# TLE6244x.net
KiCad netlist of a schematic drawn in Altium Designer
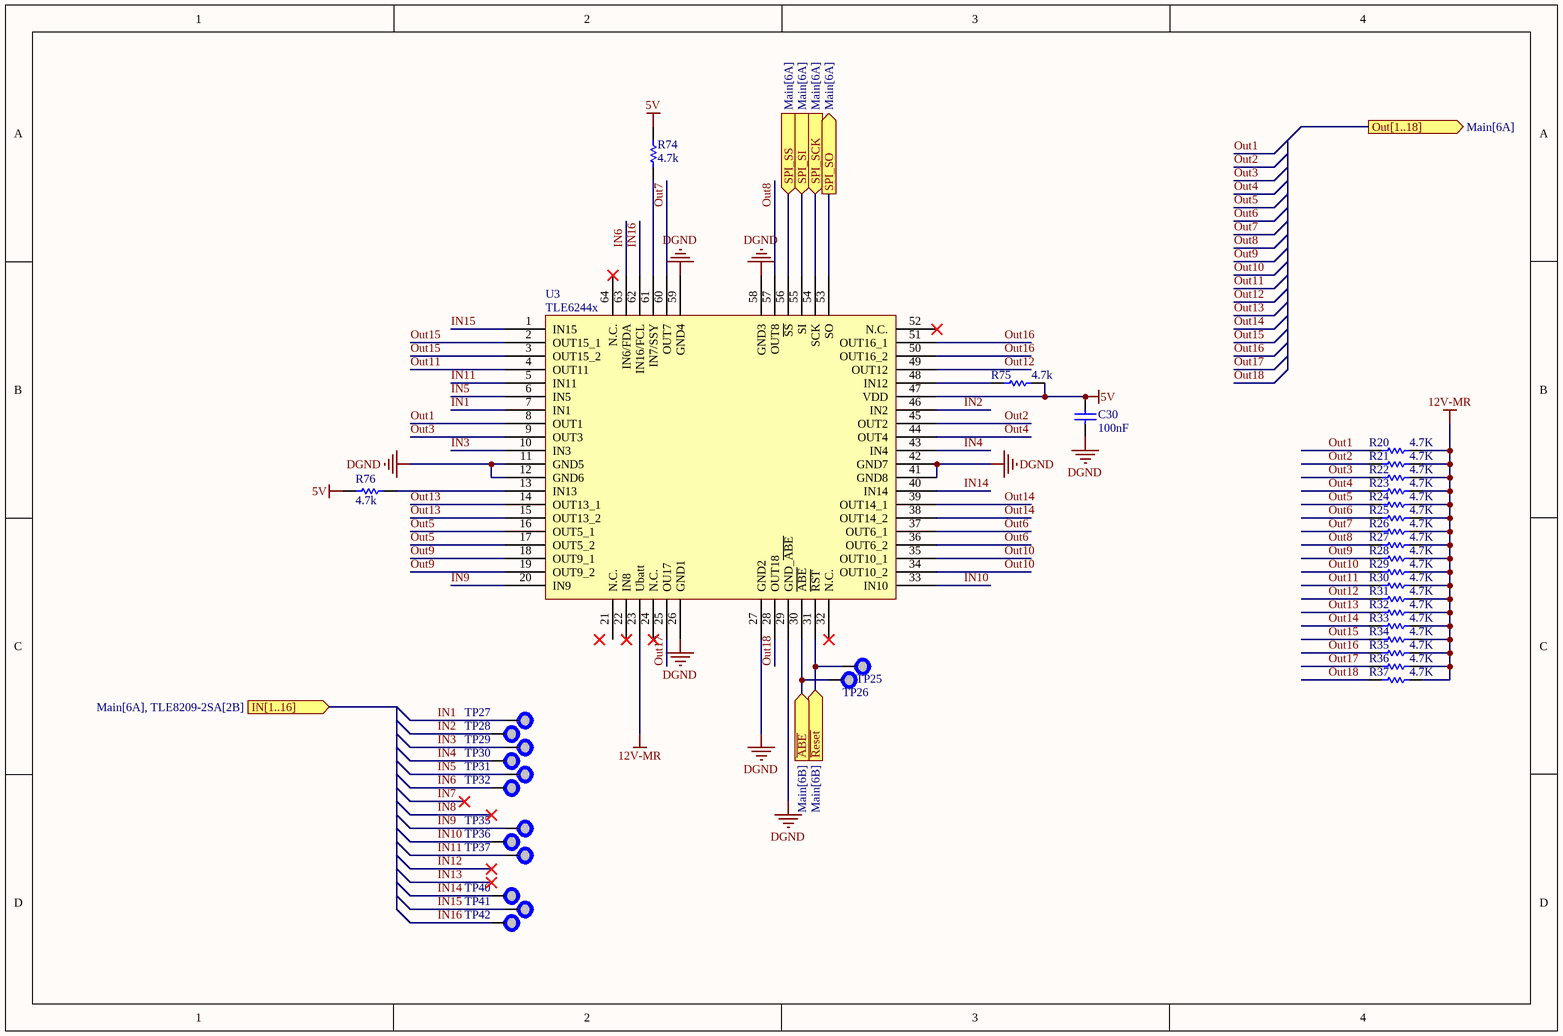
[diagram p0: TLE6244x.SchDoc]

(export (version "E")
  (design (tool "Eeschema 10.0.6"))
  (components
    (comp (ref "C30")
      (value "100nF")
      (footprint "0603C")
      (description "Capacitor")
      (fields (field (name "Comment") "CGA3E2X7R1H104K080AA") (field (name "PUBLISHER") "Altium Limited"))
      (libsource (lib "Miscellaneous Devices") (part "Cap"))
    )
    (comp (ref "R20")
      (value "4.7K")
      (footprint "0805")
      (description "Resistor")
      (fields (field (name "Comment") "Res1") (field (name "PUBLISHER") "Altium Limited"))
      (libsource (lib "Miscellaneous Devices") (part "Res1"))
    )
    (comp (ref "R21")
      (value "4.7K")
      (footprint "0805")
      (description "Resistor")
      (fields (field (name "Comment") "Res1") (field (name "PUBLISHER") "Altium Limited"))
      (libsource (lib "Miscellaneous Devices") (part "Res1"))
    )
    (comp (ref "R22")
      (value "4.7K")
      (footprint "0805")
      (description "Resistor")
      (fields (field (name "Comment") "Res1") (field (name "PUBLISHER") "Altium Limited"))
      (libsource (lib "Miscellaneous Devices") (part "Res1"))
    )
    (comp (ref "R23")
      (value "4.7K")
      (footprint "0805")
      (description "Resistor")
      (fields (field (name "Comment") "Res1") (field (name "PUBLISHER") "Altium Limited"))
      (libsource (lib "Miscellaneous Devices") (part "Res1"))
    )
    (comp (ref "R24")
      (value "4.7K")
      (footprint "0805")
      (description "Resistor")
      (fields (field (name "Comment") "Res1") (field (name "PUBLISHER") "Altium Limited"))
      (libsource (lib "Miscellaneous Devices") (part "Res1"))
    )
    (comp (ref "R25")
      (value "4.7K")
      (footprint "0805")
      (description "Resistor")
      (fields (field (name "Comment") "Res1") (field (name "PUBLISHER") "Altium Limited"))
      (libsource (lib "Miscellaneous Devices") (part "Res1"))
    )
    (comp (ref "R26")
      (value "4.7K")
      (footprint "0805")
      (description "Resistor")
      (fields (field (name "Comment") "Res1") (field (name "PUBLISHER") "Altium Limited"))
      (libsource (lib "Miscellaneous Devices") (part "Res1"))
    )
    (comp (ref "R27")
      (value "4.7K")
      (footprint "0805")
      (description "Resistor")
      (fields (field (name "Comment") "Res1") (field (name "PUBLISHER") "Altium Limited"))
      (libsource (lib "Miscellaneous Devices") (part "Res1"))
    )
    (comp (ref "R28")
      (value "4.7K")
      (footprint "0805")
      (description "Resistor")
      (fields (field (name "Comment") "Res1") (field (name "PUBLISHER") "Altium Limited"))
      (libsource (lib "Miscellaneous Devices") (part "Res1"))
    )
    (comp (ref "R29")
      (value "4.7K")
      (footprint "0805")
      (description "Resistor")
      (fields (field (name "Comment") "Res1") (field (name "PUBLISHER") "Altium Limited"))
      (libsource (lib "Miscellaneous Devices") (part "Res1"))
    )
    (comp (ref "R30")
      (value "4.7K")
      (footprint "0805")
      (description "Resistor")
      (fields (field (name "Comment") "Res1") (field (name "PUBLISHER") "Altium Limited"))
      (libsource (lib "Miscellaneous Devices") (part "Res1"))
    )
    (comp (ref "R31")
      (value "4.7K")
      (footprint "0805")
      (description "Resistor")
      (fields (field (name "Comment") "Res1") (field (name "PUBLISHER") "Altium Limited"))
      (libsource (lib "Miscellaneous Devices") (part "Res1"))
    )
    (comp (ref "R32")
      (value "4.7K")
      (footprint "0805")
      (description "Resistor")
      (fields (field (name "Comment") "Res1") (field (name "PUBLISHER") "Altium Limited"))
      (libsource (lib "Miscellaneous Devices") (part "Res1"))
    )
    (comp (ref "R33")
      (value "4.7K")
      (footprint "0805")
      (description "Resistor")
      (fields (field (name "Comment") "Res1") (field (name "PUBLISHER") "Altium Limited"))
      (libsource (lib "Miscellaneous Devices") (part "Res1"))
    )
    (comp (ref "R34")
      (value "4.7K")
      (footprint "0805")
      (description "Resistor")
      (fields (field (name "Comment") "Res1") (field (name "PUBLISHER") "Altium Limited"))
      (libsource (lib "Miscellaneous Devices") (part "Res1"))
    )
    (comp (ref "R35")
      (value "4.7K")
      (footprint "0805")
      (description "Resistor")
      (fields (field (name "Comment") "Res1") (field (name "PUBLISHER") "Altium Limited"))
      (libsource (lib "Miscellaneous Devices") (part "Res1"))
    )
    (comp (ref "R36")
      (value "4.7K")
      (footprint "0805")
      (description "Resistor")
      (fields (field (name "Comment") "Res1") (field (name "PUBLISHER") "Altium Limited"))
      (libsource (lib "Miscellaneous Devices") (part "Res1"))
    )
    (comp (ref "R37")
      (value "4.7K")
      (footprint "0805")
      (description "Resistor")
      (fields (field (name "Comment") "Res1") (field (name "PUBLISHER") "Altium Limited"))
      (libsource (lib "Miscellaneous Devices") (part "Res1"))
    )
    (comp (ref "R74")
      (value "4.7k")
      (footprint "0805")
      (description "Resistor")
      (fields (field (name "Comment") "Res1") (field (name "PUBLISHER") "Altium Limited"))
      (libsource (lib "Miscellaneous Devices") (part "Res1"))
    )
    (comp (ref "R75")
      (value "4.7k")
      (footprint "0805")
      (description "Resistor")
      (fields (field (name "Comment") "Res1") (field (name "PUBLISHER") "Altium Limited"))
      (libsource (lib "Miscellaneous Devices") (part "Res1"))
    )
    (comp (ref "R76")
      (value "4.7k")
      (footprint "0805")
      (description "Resistor")
      (fields (field (name "Comment") "Res1") (field (name "PUBLISHER") "Altium Limited"))
      (libsource (lib "Miscellaneous Devices") (part "Res1"))
    )
    (comp (ref "TP25") (value "TestPoint") (footprint "TP") (libsource (lib "SchlibV0.1") (part "TestPoint")))
    (comp (ref "TP26") (value "TestPoint") (footprint "TP") (libsource (lib "SchlibV0.1") (part "TestPoint")))
    (comp (ref "TP27") (value "TestPoint") (footprint "TP") (libsource (lib "SchlibV0.1") (part "TestPoint")))
    (comp (ref "TP28") (value "TestPoint") (footprint "TP") (libsource (lib "SchlibV0.1") (part "TestPoint")))
    (comp (ref "TP29") (value "TestPoint") (footprint "TP") (libsource (lib "SchlibV0.1") (part "TestPoint")))
    (comp (ref "TP30") (value "TestPoint") (footprint "TP") (libsource (lib "SchlibV0.1") (part "TestPoint")))
    (comp (ref "TP31") (value "TestPoint") (footprint "TP") (libsource (lib "SchlibV0.1") (part "TestPoint")))
    (comp (ref "TP32") (value "TestPoint") (footprint "TP") (libsource (lib "SchlibV0.1") (part "TestPoint")))
    (comp (ref "TP35") (value "TestPoint") (footprint "TP") (libsource (lib "SchlibV0.1") (part "TestPoint")))
    (comp (ref "TP36") (value "TestPoint") (footprint "TP") (libsource (lib "SchlibV0.1") (part "TestPoint")))
    (comp (ref "TP37") (value "TestPoint") (footprint "TP") (libsource (lib "SchlibV0.1") (part "TestPoint")))
    (comp (ref "TP40") (value "TestPoint") (footprint "TP") (libsource (lib "SchlibV0.1") (part "TestPoint")))
    (comp (ref "TP41") (value "TestPoint") (footprint "TP") (libsource (lib "SchlibV0.1") (part "TestPoint")))
    (comp (ref "TP42") (value "TestPoint") (footprint "TP") (libsource (lib "SchlibV0.1") (part "TestPoint")))
    (comp (ref "U3")
      (value "TLE6244x")
      (footprint "TLE6244")
      (description "PG-MQFP-64-10")
      (fields (field (name "MANUFACTURER") "Infineon") (field (name "PART NUMBER") "TLE6244X"))
      (libsource (lib "TLE 6244X") (part "TLE6244x"))
    )
  )
  (nets
    (net (code "1") (name "/IN1") (class "Default")
      (node (ref "TP27") (pin "1") (pintype "passive"))
      (node (ref "U3") (pin "7") (pinfunction "IN1_7") (pintype "passive"))
    )
    (net (code "2") (name "/IN2") (class "Default")
      (node (ref "TP28") (pin "1") (pintype "passive"))
      (node (ref "U3") (pin "46") (pinfunction "IN2_46") (pintype "passive"))
    )
    (net (code "3") (name "/IN3") (class "Default")
      (node (ref "TP29") (pin "1") (pintype "passive"))
      (node (ref "U3") (pin "10") (pinfunction "IN3_10") (pintype "passive"))
    )
    (net (code "4") (name "/IN4") (class "Default")
      (node (ref "TP30") (pin "1") (pintype "passive"))
      (node (ref "U3") (pin "43") (pinfunction "IN4_43") (pintype "passive"))
    )
    (net (code "5") (name "/IN5") (class "Default")
      (node (ref "TP31") (pin "1") (pintype "passive"))
      (node (ref "U3") (pin "6") (pinfunction "IN5_6") (pintype "passive"))
    )
    (net (code "6") (name "/IN6") (class "Default")
      (node (ref "TP32") (pin "1") (pintype "passive"))
      (node (ref "U3") (pin "63") (pinfunction "IN6/FDA_63") (pintype "passive"))
    )
    (net (code "9") (name "/IN9") (class "Default")
      (node (ref "TP35") (pin "1") (pintype "passive"))
      (node (ref "U3") (pin "20") (pinfunction "IN9_20") (pintype "passive"))
    )
    (net (code "10") (name "/IN10") (class "Default")
      (node (ref "TP36") (pin "1") (pintype "passive"))
      (node (ref "U3") (pin "33") (pinfunction "IN10_33") (pintype "passive"))
    )
    (net (code "11") (name "/IN11") (class "Default")
      (node (ref "TP37") (pin "1") (pintype "passive"))
      (node (ref "U3") (pin "5") (pinfunction "IN11_5") (pintype "passive"))
    )
    (net (code "14") (name "/IN14") (class "Default")
      (node (ref "TP40") (pin "1") (pintype "passive"))
      (node (ref "U3") (pin "40") (pinfunction "IN14_40") (pintype "passive"))
    )
    (net (code "15") (name "/IN15") (class "Default")
      (node (ref "TP41") (pin "1") (pintype "passive"))
      (node (ref "U3") (pin "1") (pinfunction "IN15_1") (pintype "passive"))
    )
    (net (code "16") (name "/IN16") (class "Default")
      (node (ref "TP42") (pin "1") (pintype "passive"))
      (node (ref "U3") (pin "62") (pinfunction "IN16/FCL_62") (pintype "passive"))
    )
    (net (code "18") (name "/Out1") (class "Default")
      (node (ref "R20") (pin "2") (pinfunction "2_2") (pintype "passive"))
      (node (ref "U3") (pin "8") (pinfunction "OUT1_8") (pintype "passive"))
    )
    (net (code "19") (name "/Out2") (class "Default")
      (node (ref "R21") (pin "2") (pinfunction "2_2") (pintype "passive"))
      (node (ref "U3") (pin "45") (pinfunction "OUT2_45") (pintype "passive"))
    )
    (net (code "20") (name "/Out3") (class "Default")
      (node (ref "R22") (pin "2") (pinfunction "2_2") (pintype "passive"))
      (node (ref "U3") (pin "9") (pinfunction "OUT3_9") (pintype "passive"))
    )
    (net (code "21") (name "/Out4") (class "Default")
      (node (ref "R23") (pin "2") (pinfunction "2_2") (pintype "passive"))
      (node (ref "U3") (pin "44") (pinfunction "OUT4_44") (pintype "passive"))
    )
    (net (code "22") (name "/Out5") (class "Default")
      (node (ref "R24") (pin "2") (pinfunction "2_2") (pintype "passive"))
      (node (ref "U3") (pin "16") (pinfunction "OUT5_1_16") (pintype "passive"))
      (node (ref "U3") (pin "17") (pinfunction "OUT5_2_17") (pintype "passive"))
    )
    (net (code "23") (name "/Out6") (class "Default")
      (node (ref "R25") (pin "2") (pinfunction "2_2") (pintype "passive"))
      (node (ref "U3") (pin "36") (pinfunction "OUT6_2_36") (pintype "passive"))
      (node (ref "U3") (pin "37") (pinfunction "OUT6_1_37") (pintype "passive"))
    )
    (net (code "24") (name "/Out7") (class "Default")
      (node (ref "R26") (pin "2") (pinfunction "2_2") (pintype "passive"))
      (node (ref "U3") (pin "60") (pinfunction "OUT7_60") (pintype "passive"))
    )
    (net (code "25") (name "/Out8") (class "Default")
      (node (ref "R27") (pin "2") (pinfunction "2_2") (pintype "passive"))
      (node (ref "U3") (pin "57") (pinfunction "OUT8_57") (pintype "passive"))
    )
    (net (code "26") (name "/Out9") (class "Default")
      (node (ref "R28") (pin "2") (pinfunction "2_2") (pintype "passive"))
      (node (ref "U3") (pin "18") (pinfunction "OUT9_1_18") (pintype "passive"))
      (node (ref "U3") (pin "19") (pinfunction "OUT9_2_19") (pintype "passive"))
    )
    (net (code "27") (name "/Out10") (class "Default")
      (node (ref "R29") (pin "2") (pinfunction "2_2") (pintype "passive"))
      (node (ref "U3") (pin "34") (pinfunction "OUT10_2_34") (pintype "passive"))
      (node (ref "U3") (pin "35") (pinfunction "OUT10_1_35") (pintype "passive"))
    )
    (net (code "28") (name "/Out11") (class "Default")
      (node (ref "R30") (pin "2") (pinfunction "2_2") (pintype "passive"))
      (node (ref "U3") (pin "4") (pinfunction "OUT11_4") (pintype "passive"))
    )
    (net (code "29") (name "/Out12") (class "Default")
      (node (ref "R31") (pin "2") (pinfunction "2_2") (pintype "passive"))
      (node (ref "U3") (pin "49") (pinfunction "OUT12_49") (pintype "passive"))
    )
    (net (code "30") (name "/Out13") (class "Default")
      (node (ref "R32") (pin "2") (pinfunction "2_2") (pintype "passive"))
      (node (ref "U3") (pin "14") (pinfunction "OUT13_1_14") (pintype "passive"))
      (node (ref "U3") (pin "15") (pinfunction "OUT13_2_15") (pintype "passive"))
    )
    (net (code "31") (name "/Out14") (class "Default")
      (node (ref "R33") (pin "2") (pinfunction "2_2") (pintype "passive"))
      (node (ref "U3") (pin "38") (pinfunction "OUT14_2_38") (pintype "passive"))
      (node (ref "U3") (pin "39") (pinfunction "OUT14_1_39") (pintype "passive"))
    )
    (net (code "32") (name "/Out15") (class "Default")
      (node (ref "R34") (pin "2") (pinfunction "2_2") (pintype "passive"))
      (node (ref "U3") (pin "2") (pinfunction "OUT15_1_2") (pintype "passive"))
      (node (ref "U3") (pin "3") (pinfunction "OUT15_2_3") (pintype "passive"))
    )
    (net (code "33") (name "/Out16") (class "Default")
      (node (ref "R35") (pin "2") (pinfunction "2_2") (pintype "passive"))
      (node (ref "U3") (pin "50") (pinfunction "OUT16_2_50") (pintype "passive"))
      (node (ref "U3") (pin "51") (pinfunction "OUT16_1_51") (pintype "passive"))
    )
    (net (code "34") (name "/Out17") (class "Default")
      (node (ref "R36") (pin "2") (pinfunction "2_2") (pintype "passive"))
      (node (ref "U3") (pin "25") (pinfunction "OU17_25") (pintype "passive"))
    )
    (net (code "35") (name "/Out18") (class "Default")
      (node (ref "R37") (pin "2") (pinfunction "2_2") (pintype "passive"))
      (node (ref "U3") (pin "28") (pinfunction "OUT18_28") (pintype "passive"))
    )
    (net (code "37") (name "/SPI_SCK") (class "Default")
      (node (ref "U3") (pin "54") (pinfunction "SCK_54") (pintype "passive"))
    )
    (net (code "38") (name "/SPI_SI") (class "Default")
      (node (ref "U3") (pin "55") (pinfunction "SI_55") (pintype "passive"))
    )
    (net (code "39") (name "/SPI_SO") (class "Default")
      (node (ref "U3") (pin "53") (pinfunction "SO_53") (pintype "passive"))
    )
    (net (code "40") (name "/SPI_SS") (class "Default")
      (node (ref "U3") (pin "56") (pinfunction "~{SS}_56") (pintype "passive"))
    )
    (net (code "41") (name "/~{ABE}") (class "Default")
      (node (ref "TP26") (pin "1") (pintype "passive"))
      (node (ref "U3") (pin "30") (pinfunction "~{ABE}_30") (pintype "passive"))
    )
    (net (code "42") (name "/~{Reset}") (class "Default")
      (node (ref "TP25") (pin "1") (pintype "passive"))
      (node (ref "U3") (pin "31") (pinfunction "~{RST}_31") (pintype "passive"))
    )
    (net (code "43") (name "5V") (class "Default")
      (node (ref "C30") (pin "1") (pinfunction "1_1") (pintype "passive"))
      (node (ref "R74") (pin "2") (pinfunction "2_2") (pintype "passive"))
      (node (ref "R75") (pin "1") (pinfunction "1_1") (pintype "passive"))
      (node (ref "R76") (pin "2") (pinfunction "2_2") (pintype "passive"))
      (node (ref "U3") (pin "47") (pinfunction "VDD_47") (pintype "passive"))
    )
    (net (code "44") (name "12V-MR") (class "Default")
      (node (ref "R20") (pin "1") (pinfunction "1_1") (pintype "passive"))
      (node (ref "R21") (pin "1") (pinfunction "1_1") (pintype "passive"))
      (node (ref "R22") (pin "1") (pinfunction "1_1") (pintype "passive"))
      (node (ref "R23") (pin "1") (pinfunction "1_1") (pintype "passive"))
      (node (ref "R24") (pin "1") (pinfunction "1_1") (pintype "passive"))
      (node (ref "R25") (pin "1") (pinfunction "1_1") (pintype "passive"))
      (node (ref "R26") (pin "1") (pinfunction "1_1") (pintype "passive"))
      (node (ref "R27") (pin "1") (pinfunction "1_1") (pintype "passive"))
      (node (ref "R28") (pin "1") (pinfunction "1_1") (pintype "passive"))
      (node (ref "R29") (pin "1") (pinfunction "1_1") (pintype "passive"))
      (node (ref "R30") (pin "1") (pinfunction "1_1") (pintype "passive"))
      (node (ref "R31") (pin "1") (pinfunction "1_1") (pintype "passive"))
      (node (ref "R32") (pin "1") (pinfunction "1_1") (pintype "passive"))
      (node (ref "R33") (pin "1") (pinfunction "1_1") (pintype "passive"))
      (node (ref "R34") (pin "1") (pinfunction "1_1") (pintype "passive"))
      (node (ref "R35") (pin "1") (pinfunction "1_1") (pintype "passive"))
      (node (ref "R36") (pin "1") (pinfunction "1_1") (pintype "passive"))
      (node (ref "R37") (pin "1") (pinfunction "1_1") (pintype "passive"))
      (node (ref "U3") (pin "23") (pinfunction "Ubatt_23") (pintype "passive"))
    )
    (net (code "45") (name "DGND") (class "Default")
      (node (ref "C30") (pin "2") (pinfunction "2_2") (pintype "passive"))
      (node (ref "U3") (pin "11") (pinfunction "GND5_11") (pintype "passive"))
      (node (ref "U3") (pin "12") (pinfunction "GND6_12") (pintype "passive"))
      (node (ref "U3") (pin "26") (pinfunction "GND1_26") (pintype "passive"))
      (node (ref "U3") (pin "27") (pinfunction "GND2_27") (pintype "passive"))
      (node (ref "U3") (pin "29") (pinfunction "GND_~{ABE}_29") (pintype "passive"))
      (node (ref "U3") (pin "41") (pinfunction "GND8_41") (pintype "passive"))
      (node (ref "U3") (pin "42") (pinfunction "GND7_42") (pintype "passive"))
      (node (ref "U3") (pin "58") (pinfunction "GND3_58") (pintype "passive"))
      (node (ref "U3") (pin "59") (pinfunction "GND4_59") (pintype "passive"))
    )
    (net (code "46") (name "Net-(U3-IN7{slash}SSY)") (class "Default")
      (node (ref "R74") (pin "1") (pinfunction "1_1") (pintype "passive"))
      (node (ref "U3") (pin "61") (pinfunction "IN7/SSY_61") (pintype "passive"))
    )
    (net (code "47") (name "Net-(U3-IN12)") (class "Default")
      (node (ref "R75") (pin "2") (pinfunction "2_2") (pintype "passive"))
      (node (ref "U3") (pin "48") (pinfunction "IN12_48") (pintype "passive"))
    )
    (net (code "48") (name "Net-(U3-IN13)") (class "Default")
      (node (ref "R76") (pin "1") (pinfunction "1_1") (pintype "passive"))
      (node (ref "U3") (pin "13") (pinfunction "IN13_13") (pintype "passive"))
    )
    (net (code "49") (name "gnd") (class "Default")
      (node (ref "U3") (pin "65") (pinfunction "GND_65") (pintype "passive"))
    )
    (net (code "50") (name "unconnected-(U3-IN8-Pad22)") (class "Default")
      (node (ref "U3") (pin "22") (pinfunction "IN8_22") (pintype "passive+no_connect"))
    )
    (net (code "51") (name "unconnected-(U3-N.C.-Pad21)") (class "Default")
      (node (ref "U3") (pin "21") (pinfunction "N.C._21") (pintype "passive"))
    )
    (net (code "52") (name "unconnected-(U3-N.C.-Pad24)") (class "Default")
      (node (ref "U3") (pin "24") (pinfunction "N.C._24") (pintype "passive+no_connect"))
    )
    (net (code "53") (name "unconnected-(U3-N.C.-Pad32)") (class "Default")
      (node (ref "U3") (pin "32") (pinfunction "N.C._32") (pintype "passive+no_connect"))
    )
    (net (code "54") (name "unconnected-(U3-N.C.-Pad52)") (class "Default")
      (node (ref "U3") (pin "52") (pinfunction "N.C._52") (pintype "passive+no_connect"))
    )
    (net (code "55") (name "unconnected-(U3-N.C.-Pad64)") (class "Default")
      (node (ref "U3") (pin "64") (pinfunction "N.C._64") (pintype "passive+no_connect"))
    )
  )
)
